# indication.net
KiCad netlist of a schematic drawn in Altium Designer
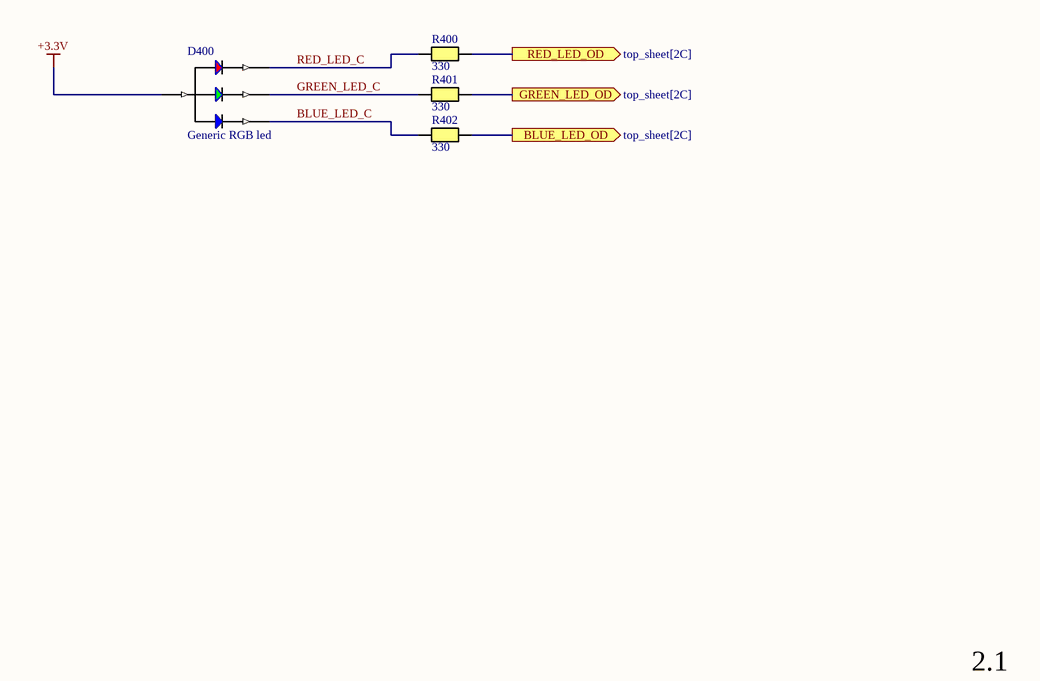
[diagram p0: indication.SchDoc]

(export (version "E")
  (design (tool "Eeschema 10.0.6"))
  (components
    (comp (ref "D400")
      (value "Generic RGB led")
      (footprint "RGB throu hole 90 deg")
      (libsource (lib "Optical") (part "RGB led"))
    )
    (comp (ref "R400")
      (value "330")
      (footprint "RESC0603(1608)_N")
      (description "Resistor Medium Density")
      (libsource (lib "Discrete") (part "Resistor M"))
    )
    (comp (ref "R401")
      (value "330")
      (footprint "RESC0603(1608)_N")
      (description "Resistor Medium Density")
      (libsource (lib "Discrete") (part "Resistor M"))
    )
    (comp (ref "R402")
      (value "330")
      (footprint "RESC0603(1608)_N")
      (description "Resistor Medium Density")
      (libsource (lib "Discrete") (part "Resistor M"))
    )
  )
  (nets
    (net (code "1") (name "+3.3V") (class "Default")
      (node (ref "D400") (pin "CA") (pinfunction "CA_CA") (pintype "input"))
    )
    (net (code "2") (name "/BLUE_LED_C") (class "Default")
      (node (ref "D400") (pin "BC") (pinfunction "BC_BC") (pintype "output"))
      (node (ref "R402") (pin "1") (pinfunction "1_1") (pintype "passive"))
    )
    (net (code "3") (name "/BLUE_LED_OD") (class "Default")
      (node (ref "R402") (pin "2") (pinfunction "2_2") (pintype "passive"))
    )
    (net (code "4") (name "/GREEN_LED_C") (class "Default")
      (node (ref "D400") (pin "GC") (pinfunction "GC_GC") (pintype "output"))
      (node (ref "R401") (pin "1") (pinfunction "1_1") (pintype "passive"))
    )
    (net (code "5") (name "/GREEN_LED_OD") (class "Default")
      (node (ref "R401") (pin "2") (pinfunction "2_2") (pintype "passive"))
    )
    (net (code "6") (name "/RED_LED_C") (class "Default")
      (node (ref "D400") (pin "RC") (pinfunction "RC_RC") (pintype "output"))
      (node (ref "R400") (pin "1") (pinfunction "1_1") (pintype "passive"))
    )
    (net (code "7") (name "/RED_LED_OD") (class "Default")
      (node (ref "R400") (pin "2") (pinfunction "2_2") (pintype "passive"))
    )
  )
)
